# voltage_sensor_HiZ_LV_OpAmp.net
KiCad netlist of a schematic drawn in Altium Designer
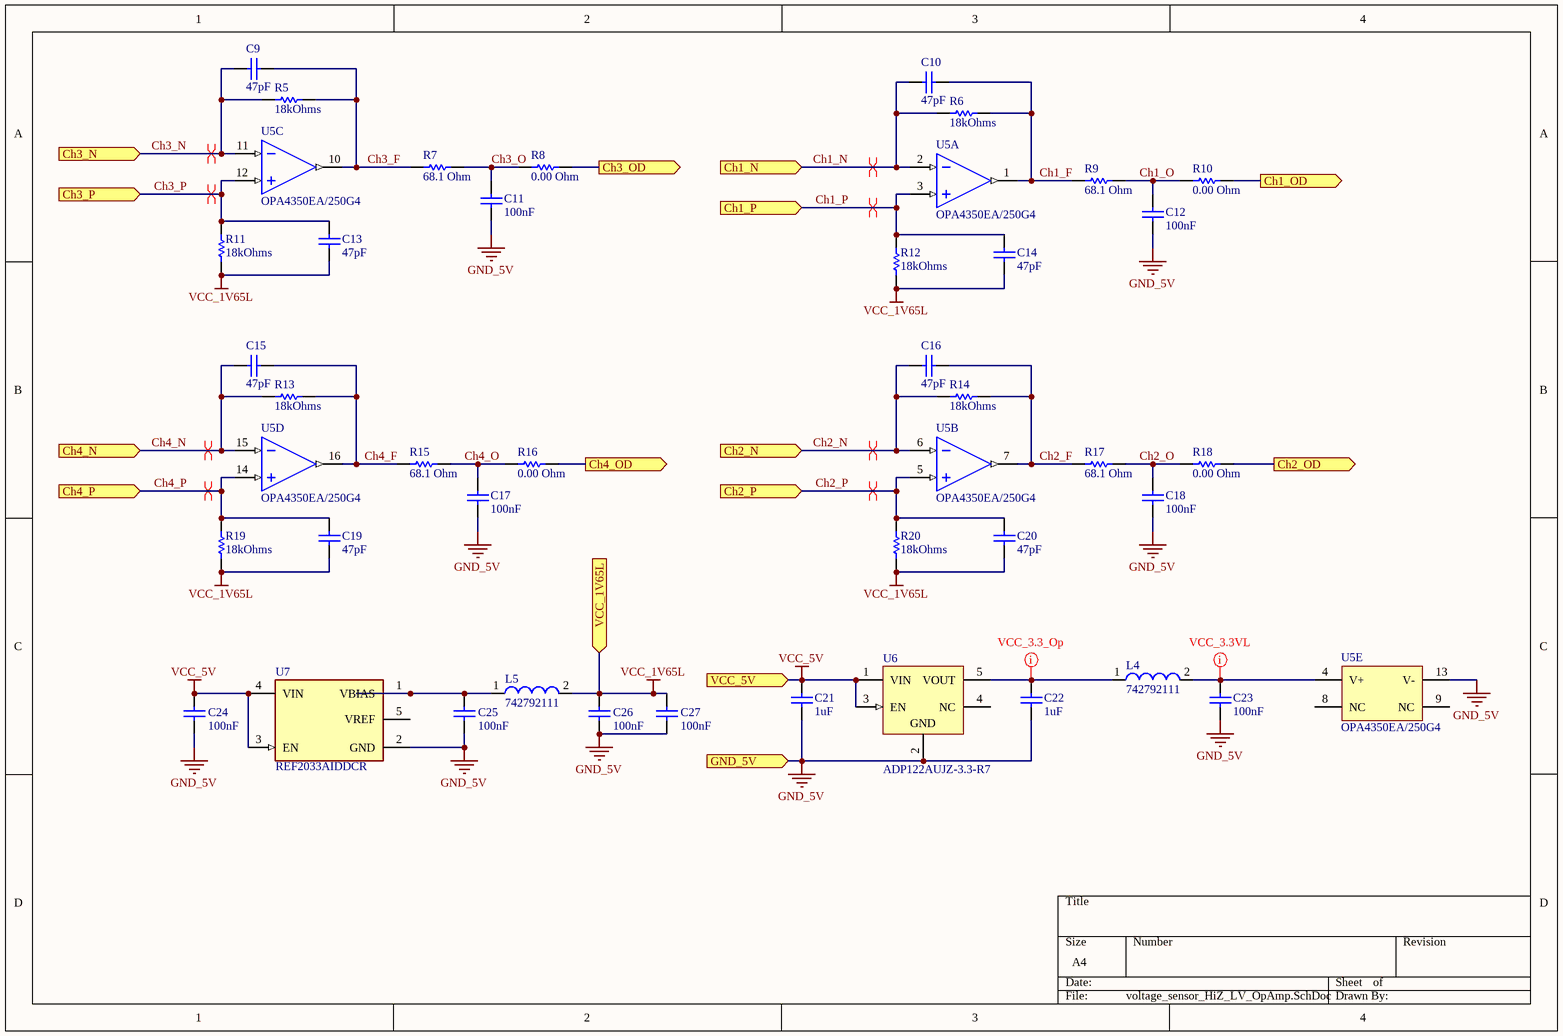
[diagram p0: voltage_sensor_HiZ_LV_OpAmp.SchDoc]

(export (version "E")
  (design (tool "Eeschema 10.0.6"))
  (components
    (comp (ref "C9")
      (value "47pF")
      (footprint "CAPC0603(1608)100_L")
      (description "CAP 47pF 50V ±5% 0603 (1608 Metric) Thickness 1mm SMD")
      (fields (field (name "TOLERANCE") "Â±5%") (field (name "Comment") "CAP 47pF 50V 0603(1608)"))
      (libsource (lib "Altium Content Vault") (part "CAP"))
    )
    (comp (ref "C10")
      (value "47pF")
      (footprint "CAPC0603(1608)100_L")
      (description "CAP 47pF 50V ±5% 0603 (1608 Metric) Thickness 1mm SMD")
      (fields (field (name "TOLERANCE") "Â±5%") (field (name "Comment") "CAP 47pF 50V 0603(1608)"))
      (libsource (lib "Altium Content Vault") (part "CAP"))
    )
    (comp (ref "C11")
      (value "100nF")
      (footprint "CAPC0603(1608)100_L")
      (description "CAP 100nF 10V ±10% 0603 (1608 Metric) Thickness 1mm SMD")
      (fields (field (name "TOLERANCE") "Â±10%") (field (name "Comment") "CAP 100nF 10V 0603(1608)"))
      (libsource (lib "Altium Content Vault") (part "CAP"))
    )
    (comp (ref "C12")
      (value "100nF")
      (footprint "CAPC0603(1608)100_L")
      (description "CAP 100nF 10V ±10% 0603 (1608 Metric) Thickness 1mm SMD")
      (fields (field (name "TOLERANCE") "Â±10%") (field (name "Comment") "CAP 100nF 10V 0603(1608)"))
      (libsource (lib "Altium Content Vault") (part "CAP"))
    )
    (comp (ref "C13")
      (value "47pF")
      (footprint "CAPC0603(1608)100_L")
      (description "CAP 47pF 50V ±5% 0603 (1608 Metric) Thickness 1mm SMD")
      (fields (field (name "TOLERANCE") "Â±5%") (field (name "Comment") "CAP 47pF 50V 0603(1608)"))
      (libsource (lib "Altium Content Vault") (part "CAP"))
    )
    (comp (ref "C14")
      (value "47pF")
      (footprint "CAPC0603(1608)100_L")
      (description "CAP 47pF 50V ±5% 0603 (1608 Metric) Thickness 1mm SMD")
      (fields (field (name "TOLERANCE") "Â±5%") (field (name "Comment") "CAP 47pF 50V 0603(1608)"))
      (libsource (lib "Altium Content Vault") (part "CAP"))
    )
    (comp (ref "C15")
      (value "47pF")
      (footprint "CAPC0603(1608)100_L")
      (description "CAP 47pF 50V ±5% 0603 (1608 Metric) Thickness 1mm SMD")
      (fields (field (name "TOLERANCE") "Â±5%") (field (name "Comment") "CAP 47pF 50V 0603(1608)"))
      (libsource (lib "Altium Content Vault") (part "CAP"))
    )
    (comp (ref "C16")
      (value "47pF")
      (footprint "CAPC0603(1608)100_L")
      (description "CAP 47pF 50V ±5% 0603 (1608 Metric) Thickness 1mm SMD")
      (fields (field (name "TOLERANCE") "Â±5%") (field (name "Comment") "CAP 47pF 50V 0603(1608)"))
      (libsource (lib "Altium Content Vault") (part "CAP"))
    )
    (comp (ref "C17")
      (value "100nF")
      (footprint "CAPC0603(1608)100_L")
      (description "CAP 100nF 10V ±10% 0603 (1608 Metric) Thickness 1mm SMD")
      (fields (field (name "TOLERANCE") "Â±10%") (field (name "Comment") "CAP 100nF 10V 0603(1608)"))
      (libsource (lib "Altium Content Vault") (part "CAP"))
    )
    (comp (ref "C18")
      (value "100nF")
      (footprint "CAPC0603(1608)100_L")
      (description "CAP 100nF 10V ±10% 0603 (1608 Metric) Thickness 1mm SMD")
      (fields (field (name "TOLERANCE") "Â±10%") (field (name "Comment") "CAP 100nF 10V 0603(1608)"))
      (libsource (lib "Altium Content Vault") (part "CAP"))
    )
    (comp (ref "C19")
      (value "47pF")
      (footprint "CAPC0603(1608)100_L")
      (description "CAP 47pF 50V ±5% 0603 (1608 Metric) Thickness 1mm SMD")
      (fields (field (name "TOLERANCE") "Â±5%") (field (name "Comment") "CAP 47pF 50V 0603(1608)"))
      (libsource (lib "Altium Content Vault") (part "CAP"))
    )
    (comp (ref "C20")
      (value "47pF")
      (footprint "CAPC0603(1608)100_L")
      (description "CAP 47pF 50V ±5% 0603 (1608 Metric) Thickness 1mm SMD")
      (fields (field (name "TOLERANCE") "Â±5%") (field (name "Comment") "CAP 47pF 50V 0603(1608)"))
      (libsource (lib "Altium Content Vault") (part "CAP"))
    )
    (comp (ref "C21")
      (value "1uF")
      (footprint "CAPC0603(1608)100_N")
      (description "CAP 1uF 50V ±20% 0603 (1608 Metric) Thickness 1mm SMD")
      (fields (field (name "TOLERANCE") "Â±20%") (field (name "Comment") "CAP 1uF 50V 0603(1608)"))
      (libsource (lib "Altium Content Vault") (part "CAP"))
    )
    (comp (ref "C22")
      (value "1uF")
      (footprint "CAPC0603(1608)100_N")
      (description "CAP 1uF 50V ±20% 0603 (1608 Metric) Thickness 1mm SMD")
      (fields (field (name "TOLERANCE") "Â±20%") (field (name "Comment") "CAP 1uF 50V 0603(1608)"))
      (libsource (lib "Altium Content Vault") (part "CAP"))
    )
    (comp (ref "C23")
      (value "100nF")
      (footprint "CAPC0603(1608)100_L")
      (description "CAP 100nF 10V ±10% 0603 (1608 Metric) Thickness 1mm SMD")
      (fields (field (name "TOLERANCE") "Â±10%") (field (name "Comment") "CAP 100nF 10V 0603(1608)"))
      (libsource (lib "Altium Content Vault") (part "CAP"))
    )
    (comp (ref "C24")
      (value "100nF")
      (footprint "CAPC0603(1608)100_N")
      (description "CAP 100nF 10V ±10% 0603 (1608 Metric) Thickness 1mm SMD")
      (fields (field (name "TOLERANCE") "Â±10%") (field (name "Comment") "CAP 100nF 10V 0603(1608)"))
      (libsource (lib "Altium Content Vault") (part "CAP"))
    )
    (comp (ref "C25")
      (value "100nF")
      (footprint "CAPC0603(1608)100_N")
      (description "CAP 100nF 10V ±10% 0603 (1608 Metric) Thickness 1mm SMD")
      (fields (field (name "TOLERANCE") "Â±10%") (field (name "Comment") "CAP 100nF 10V 0603(1608)"))
      (libsource (lib "Altium Content Vault") (part "CAP"))
    )
    (comp (ref "C26")
      (value "100nF")
      (footprint "CAPC0603(1608)100_L")
      (description "CAP 100nF 10V ±10% 0603 (1608 Metric) Thickness 1mm SMD")
      (fields (field (name "TOLERANCE") "Â±10%") (field (name "Comment") "CAP 100nF 10V 0603(1608)"))
      (libsource (lib "Altium Content Vault") (part "CAP"))
    )
    (comp (ref "C27")
      (value "100nF")
      (footprint "CAPC0603(1608)100_L")
      (description "CAP 100nF 10V ±10% 0603 (1608 Metric) Thickness 1mm SMD")
      (fields (field (name "TOLERANCE") "Â±10%") (field (name "Comment") "CAP 100nF 10V 0603(1608)"))
      (libsource (lib "Altium Content Vault") (part "CAP"))
    )
    (comp (ref "L4")
      (value "742792111")
      (footprint "SMD-1206")
      (description "SMD EMI Suppression Ferrite Bead WE-CBF, Z = 26 Ohm")
      (libsource (lib "Altium Content Vault") (part "PAS-IND-INDUCTOR-2"))
    )
    (comp (ref "L5")
      (value "742792111")
      (footprint "SMD-1206")
      (description "SMD EMI Suppression Ferrite Bead WE-CBF, Z = 26 Ohm")
      (libsource (lib "Altium Content Vault") (part "PAS-IND-INDUCTOR-2"))
    )
    (comp (ref "R5")
      (value "RC0603FR-0718KL")
      (footprint "RESC1608X55X25LL10T15")
      (description "Chip Resistor, 18 KOhm, +/- 1%, 0.1 W, -55 to 155 degC, 0603 (1608 Metric), RoHS, Tape and Reel")
      (fields
        (field (name "TOLERANCE") "1%")
        (field (name "MANUFACTURER") "Yageo")
        (field (name "RESISTANCE") "18kOhms")
      )
      (libsource (lib "Altium Content Vault") (part "RES-2"))
    )
    (comp (ref "R6")
      (value "RC0603FR-0718KL")
      (footprint "RESC1608X55X25LL10T15")
      (description "Chip Resistor, 18 KOhm, +/- 1%, 0.1 W, -55 to 155 degC, 0603 (1608 Metric), RoHS, Tape and Reel")
      (fields
        (field (name "TOLERANCE") "1%")
        (field (name "MANUFACTURER") "Yageo")
        (field (name "RESISTANCE") "18kOhms")
      )
      (libsource (lib "Altium Content Vault") (part "RES-2"))
    )
    (comp (ref "R7")
      (value "68.1 Ohm")
      (footprint "RESC1608X55X30LL15T15")
      (fields
        (field (name "MANUFACTURER") "Panasonic")
        (field (name "PART NUMBER") "ERJ-3EKF68R1V")
        (field (name "TOLERANCE") "1%")
      )
      (libsource (lib "Altium Content Vault") (part "RES"))
    )
    (comp (ref "R8")
      (value "0.00 Ohm")
      (footprint "RESC0603(1608)_L")
      (description "Jumper 0603 (1608 Metric)")
      (fields (field (name "POWER") "None") (field (name "Comment") "Jumper 0603(1608)"))
      (libsource (lib "Altium Content Vault") (part "RES"))
    )
    (comp (ref "R9")
      (value "68.1 Ohm")
      (footprint "RESC1608X55X30LL15T15")
      (fields
        (field (name "MANUFACTURER") "Panasonic")
        (field (name "PART NUMBER") "ERJ-3EKF68R1V")
        (field (name "TOLERANCE") "1%")
      )
      (libsource (lib "Altium Content Vault") (part "RES"))
    )
    (comp (ref "R10")
      (value "0.00 Ohm")
      (footprint "RESC0603(1608)_L")
      (description "Jumper 0603 (1608 Metric)")
      (fields (field (name "POWER") "None") (field (name "Comment") "Jumper 0603(1608)"))
      (libsource (lib "Altium Content Vault") (part "RES"))
    )
    (comp (ref "R11")
      (value "RC0603FR-0718KL")
      (footprint "RESC1608X55X25LL10T15")
      (description "Chip Resistor, 18 KOhm, +/- 1%, 0.1 W, -55 to 155 degC, 0603 (1608 Metric), RoHS, Tape and Reel")
      (fields
        (field (name "TOLERANCE") "1%")
        (field (name "MANUFACTURER") "Yageo")
        (field (name "RESISTANCE") "18kOhms")
      )
      (libsource (lib "Altium Content Vault") (part "RES-2"))
    )
    (comp (ref "R12")
      (value "RC0603FR-0718KL")
      (footprint "RESC1608X55X25LL10T15")
      (description "Chip Resistor, 18 KOhm, +/- 1%, 0.1 W, -55 to 155 degC, 0603 (1608 Metric), RoHS, Tape and Reel")
      (fields
        (field (name "TOLERANCE") "1%")
        (field (name "MANUFACTURER") "Yageo")
        (field (name "RESISTANCE") "18kOhms")
      )
      (libsource (lib "Altium Content Vault") (part "RES-2"))
    )
    (comp (ref "R13")
      (value "RC0603FR-0718KL")
      (footprint "RESC1608X55X25LL10T15")
      (description "Chip Resistor, 18 KOhm, +/- 1%, 0.1 W, -55 to 155 degC, 0603 (1608 Metric), RoHS, Tape and Reel")
      (fields
        (field (name "TOLERANCE") "1%")
        (field (name "MANUFACTURER") "Yageo")
        (field (name "RESISTANCE") "18kOhms")
      )
      (libsource (lib "Altium Content Vault") (part "RES-2"))
    )
    (comp (ref "R14")
      (value "RC0603FR-0718KL")
      (footprint "RESC1608X55X25LL10T15")
      (description "Chip Resistor, 18 KOhm, +/- 1%, 0.1 W, -55 to 155 degC, 0603 (1608 Metric), RoHS, Tape and Reel")
      (fields
        (field (name "TOLERANCE") "1%")
        (field (name "MANUFACTURER") "Yageo")
        (field (name "RESISTANCE") "18kOhms")
      )
      (libsource (lib "Altium Content Vault") (part "RES-2"))
    )
    (comp (ref "R15")
      (value "68.1 Ohm")
      (footprint "RESC1608X55X30LL15T15")
      (fields
        (field (name "MANUFACTURER") "Panasonic")
        (field (name "PART NUMBER") "ERJ-3EKF68R1V")
        (field (name "TOLERANCE") "1%")
      )
      (libsource (lib "Altium Content Vault") (part "RES"))
    )
    (comp (ref "R16")
      (value "0.00 Ohm")
      (footprint "RESC0603(1608)_L")
      (description "Jumper 0603 (1608 Metric)")
      (fields (field (name "POWER") "None") (field (name "Comment") "Jumper 0603(1608)"))
      (libsource (lib "Altium Content Vault") (part "RES"))
    )
    (comp (ref "R17")
      (value "68.1 Ohm")
      (footprint "RESC1608X55X30LL15T15")
      (fields
        (field (name "MANUFACTURER") "Panasonic")
        (field (name "PART NUMBER") "ERJ-3EKF68R1V")
        (field (name "TOLERANCE") "1%")
      )
      (libsource (lib "Altium Content Vault") (part "RES"))
    )
    (comp (ref "R18")
      (value "0.00 Ohm")
      (footprint "RESC0603(1608)_L")
      (description "Jumper 0603 (1608 Metric)")
      (fields (field (name "POWER") "None") (field (name "Comment") "Jumper 0603(1608)"))
      (libsource (lib "Altium Content Vault") (part "RES"))
    )
    (comp (ref "R19")
      (value "RC0603FR-0718KL")
      (footprint "RESC1608X55X25LL10T15")
      (description "Chip Resistor, 18 KOhm, +/- 1%, 0.1 W, -55 to 155 degC, 0603 (1608 Metric), RoHS, Tape and Reel")
      (fields
        (field (name "TOLERANCE") "1%")
        (field (name "MANUFACTURER") "Yageo")
        (field (name "RESISTANCE") "18kOhms")
      )
      (libsource (lib "Altium Content Vault") (part "RES-2"))
    )
    (comp (ref "R20")
      (value "RC0603FR-0718KL")
      (footprint "RESC1608X55X25LL10T15")
      (description "Chip Resistor, 18 KOhm, +/- 1%, 0.1 W, -55 to 155 degC, 0603 (1608 Metric), RoHS, Tape and Reel")
      (fields
        (field (name "TOLERANCE") "1%")
        (field (name "MANUFACTURER") "Yageo")
        (field (name "RESISTANCE") "18kOhms")
      )
      (libsource (lib "Altium Content Vault") (part "RES-2"))
    )
    (comp (ref "U5")
      (value "OPA4350EA/250G4")
      (footprint "TI-DBQ16_L")
      (fields (field (name "MANUFACTURER") "Texas Instruments"))
      (libsource (lib "Altium Content Vault") (part "TI-OPA4XXX-XX16"))
    )
    (comp (ref "U6")
      (value "ADP122AUJZ-3.3-R7")
      (footprint "ADI-UJ-5_N")
      (fields (field (name "MANUFACTURER") "Analog Devices"))
      (libsource (lib "Altium Content Vault") (part "ADI-ADP1XX-UJ-5"))
    )
    (comp (ref "U7")
      (value "REF2033AIDDCR")
      (footprint "FP-DDC0005A-IPC_C")
      (description "IC VREF SERIES 1.65V/3.3V 5SOT")
      (fields
        (field (name "OCTOPART") "https://octopart.com/ref2033aiddcr-texas+instruments-46921199")
        (field (name "MANUFACTURER") "Texas Instruments")
      )
      (libsource (lib "Altium Content Vault") (part "d9fc07eafd300fec854b4093a15f761"))
    )
  )
  (nets
    (net (code "1") (name "/Ch1_F") (class "Default")
      (node (ref "C10") (pin "2") (pinfunction "2_2") (pintype "passive"))
      (node (ref "R6") (pin "1") (pinfunction "1_1") (pintype "passive"))
      (node (ref "R9") (pin "2") (pinfunction "2_2") (pintype "passive"))
      (node (ref "U5") (pin "1") (pinfunction "OUT_A_1") (pintype "output"))
    )
    (net (code "2") (name "/Ch1_N") (class "Default")
      (node (ref "C10") (pin "1") (pinfunction "1_1") (pintype "passive"))
      (node (ref "R6") (pin "2") (pinfunction "2_2") (pintype "passive"))
      (node (ref "U5") (pin "2") (pinfunction "IN_A-_2") (pintype "input"))
    )
    (net (code "3") (name "/Ch1_O") (class "Default")
      (node (ref "C12") (pin "2") (pinfunction "2_2") (pintype "passive"))
      (node (ref "R10") (pin "2") (pinfunction "2_2") (pintype "passive"))
      (node (ref "R9") (pin "1") (pinfunction "1_1") (pintype "passive"))
    )
    (net (code "4") (name "/Ch1_OD") (class "Default")
      (node (ref "R10") (pin "1") (pinfunction "1_1") (pintype "passive"))
    )
    (net (code "5") (name "/Ch1_P") (class "Default")
      (node (ref "C14") (pin "1") (pinfunction "1_1") (pintype "passive"))
      (node (ref "R12") (pin "1") (pinfunction "1_1") (pintype "passive"))
      (node (ref "U5") (pin "3") (pinfunction "IN_A+_3") (pintype "input"))
    )
    (net (code "6") (name "/Ch2_F") (class "Default")
      (node (ref "C16") (pin "2") (pinfunction "2_2") (pintype "passive"))
      (node (ref "R14") (pin "1") (pinfunction "1_1") (pintype "passive"))
      (node (ref "R17") (pin "2") (pinfunction "2_2") (pintype "passive"))
      (node (ref "U5") (pin "7") (pinfunction "OUT_B_7") (pintype "output"))
    )
    (net (code "7") (name "/Ch2_N") (class "Default")
      (node (ref "C16") (pin "1") (pinfunction "1_1") (pintype "passive"))
      (node (ref "R14") (pin "2") (pinfunction "2_2") (pintype "passive"))
      (node (ref "U5") (pin "6") (pinfunction "IN_B-_6") (pintype "input"))
    )
    (net (code "8") (name "/Ch2_O") (class "Default")
      (node (ref "C18") (pin "2") (pinfunction "2_2") (pintype "passive"))
      (node (ref "R17") (pin "1") (pinfunction "1_1") (pintype "passive"))
      (node (ref "R18") (pin "2") (pinfunction "2_2") (pintype "passive"))
    )
    (net (code "9") (name "/Ch2_OD") (class "Default")
      (node (ref "R18") (pin "1") (pinfunction "1_1") (pintype "passive"))
    )
    (net (code "10") (name "/Ch2_P") (class "Default")
      (node (ref "C20") (pin "1") (pinfunction "1_1") (pintype "passive"))
      (node (ref "R20") (pin "1") (pinfunction "1_1") (pintype "passive"))
      (node (ref "U5") (pin "5") (pinfunction "IN_B+_5") (pintype "input"))
    )
    (net (code "11") (name "/Ch3_F") (class "Default")
      (node (ref "C9") (pin "2") (pinfunction "2_2") (pintype "passive"))
      (node (ref "R5") (pin "1") (pinfunction "1_1") (pintype "passive"))
      (node (ref "R7") (pin "2") (pinfunction "2_2") (pintype "passive"))
      (node (ref "U5") (pin "10") (pinfunction "OUT_C_10") (pintype "output"))
    )
    (net (code "12") (name "/Ch3_N") (class "Default")
      (node (ref "C9") (pin "1") (pinfunction "1_1") (pintype "passive"))
      (node (ref "R5") (pin "2") (pinfunction "2_2") (pintype "passive"))
      (node (ref "U5") (pin "11") (pinfunction "IN_C-_11") (pintype "input"))
    )
    (net (code "13") (name "/Ch3_O") (class "Default")
      (node (ref "C11") (pin "2") (pinfunction "2_2") (pintype "passive"))
      (node (ref "R7") (pin "1") (pinfunction "1_1") (pintype "passive"))
      (node (ref "R8") (pin "2") (pinfunction "2_2") (pintype "passive"))
    )
    (net (code "14") (name "/Ch3_OD") (class "Default")
      (node (ref "R8") (pin "1") (pinfunction "1_1") (pintype "passive"))
    )
    (net (code "15") (name "/Ch3_P") (class "Default")
      (node (ref "C13") (pin "1") (pinfunction "1_1") (pintype "passive"))
      (node (ref "R11") (pin "1") (pinfunction "1_1") (pintype "passive"))
      (node (ref "U5") (pin "12") (pinfunction "IN_C+_12") (pintype "input"))
    )
    (net (code "16") (name "/Ch4_F") (class "Default")
      (node (ref "C15") (pin "2") (pinfunction "2_2") (pintype "passive"))
      (node (ref "R13") (pin "1") (pinfunction "1_1") (pintype "passive"))
      (node (ref "R15") (pin "2") (pinfunction "2_2") (pintype "passive"))
      (node (ref "U5") (pin "16") (pinfunction "OUT_D_16") (pintype "output"))
    )
    (net (code "17") (name "/Ch4_N") (class "Default")
      (node (ref "C15") (pin "1") (pinfunction "1_1") (pintype "passive"))
      (node (ref "R13") (pin "2") (pinfunction "2_2") (pintype "passive"))
      (node (ref "U5") (pin "15") (pinfunction "IN_D-_15") (pintype "input"))
    )
    (net (code "18") (name "/Ch4_O") (class "Default")
      (node (ref "C17") (pin "2") (pinfunction "2_2") (pintype "passive"))
      (node (ref "R15") (pin "1") (pinfunction "1_1") (pintype "passive"))
      (node (ref "R16") (pin "2") (pinfunction "2_2") (pintype "passive"))
    )
    (net (code "19") (name "/Ch4_OD") (class "Default")
      (node (ref "R16") (pin "1") (pinfunction "1_1") (pintype "passive"))
    )
    (net (code "20") (name "/Ch4_P") (class "Default")
      (node (ref "C19") (pin "1") (pinfunction "1_1") (pintype "passive"))
      (node (ref "R19") (pin "1") (pinfunction "1_1") (pintype "passive"))
      (node (ref "U5") (pin "14") (pinfunction "IN_D+_14") (pintype "input"))
    )
    (net (code "21") (name "GND_5V") (class "Default")
      (node (ref "C11") (pin "1") (pinfunction "1_1") (pintype "passive"))
      (node (ref "C12") (pin "1") (pinfunction "1_1") (pintype "passive"))
      (node (ref "C17") (pin "1") (pinfunction "1_1") (pintype "passive"))
      (node (ref "C18") (pin "1") (pinfunction "1_1") (pintype "passive"))
      (node (ref "C21") (pin "1") (pinfunction "1_1") (pintype "passive"))
      (node (ref "C22") (pin "1") (pinfunction "1_1") (pintype "passive"))
      (node (ref "C23") (pin "1") (pinfunction "1_1") (pintype "passive"))
      (node (ref "C24") (pin "1") (pinfunction "1_1") (pintype "passive"))
      (node (ref "C25") (pin "1") (pinfunction "1_1") (pintype "passive"))
      (node (ref "C26") (pin "1") (pinfunction "1_1") (pintype "passive"))
      (node (ref "C27") (pin "1") (pinfunction "1_1") (pintype "passive"))
      (node (ref "U5") (pin "13") (pinfunction "V-_13") (pintype "power_in"))
      (node (ref "U6") (pin "2") (pinfunction "GND_2") (pintype "power_in"))
      (node (ref "U7") (pin "2") (pinfunction "GND_2") (pintype "power_in"))
    )
    (net (code "22") (name "Net-(U5E-V+)") (class "Default")
      (node (ref "C23") (pin "2") (pinfunction "2_2") (pintype "passive"))
      (node (ref "L4") (pin "2") (pinfunction "2_2") (pintype "passive"))
      (node (ref "U5") (pin "4") (pinfunction "V+_4") (pintype "power_in"))
    )
    (net (code "23") (name "Net-(U6-VOUT)") (class "Default")
      (node (ref "C22") (pin "2") (pinfunction "2_2") (pintype "passive"))
      (node (ref "L4") (pin "1") (pinfunction "1_1") (pintype "passive"))
      (node (ref "U6") (pin "5") (pinfunction "VOUT_5") (pintype "power_in"))
    )
    (net (code "24") (name "Net-(U7-VBIAS)") (class "Default")
      (node (ref "C25") (pin "2") (pinfunction "2_2") (pintype "passive"))
      (node (ref "L5") (pin "1") (pinfunction "1_1") (pintype "passive"))
      (node (ref "U7") (pin "1") (pinfunction "VBIAS_1") (pintype "power_in"))
    )
    (net (code "25") (name "VCC_1V65L") (class "Default")
      (node (ref "C13") (pin "2") (pinfunction "2_2") (pintype "passive"))
      (node (ref "C14") (pin "2") (pinfunction "2_2") (pintype "passive"))
      (node (ref "C19") (pin "2") (pinfunction "2_2") (pintype "passive"))
      (node (ref "C20") (pin "2") (pinfunction "2_2") (pintype "passive"))
      (node (ref "C26") (pin "2") (pinfunction "2_2") (pintype "passive"))
      (node (ref "C27") (pin "2") (pinfunction "2_2") (pintype "passive"))
      (node (ref "L5") (pin "2") (pinfunction "2_2") (pintype "passive"))
      (node (ref "R11") (pin "2") (pinfunction "2_2") (pintype "passive"))
      (node (ref "R12") (pin "2") (pinfunction "2_2") (pintype "passive"))
      (node (ref "R19") (pin "2") (pinfunction "2_2") (pintype "passive"))
      (node (ref "R20") (pin "2") (pinfunction "2_2") (pintype "passive"))
    )
    (net (code "26") (name "VCC_5V") (class "Default")
      (node (ref "C21") (pin "2") (pinfunction "2_2") (pintype "passive"))
      (node (ref "C24") (pin "2") (pinfunction "2_2") (pintype "passive"))
      (node (ref "U6") (pin "1") (pinfunction "VIN_1") (pintype "power_in"))
      (node (ref "U6") (pin "3") (pinfunction "EN_3") (pintype "input"))
      (node (ref "U7") (pin "3") (pinfunction "EN_3") (pintype "input"))
      (node (ref "U7") (pin "4") (pinfunction "VIN_4") (pintype "power_in"))
    )
    (net (code "27") (name "unconnected-(U5E-NC-Pad8)") (class "Default")
      (node (ref "U5") (pin "8") (pinfunction "NC_8") (pintype "passive"))
    )
    (net (code "28") (name "unconnected-(U5E-NC-Pad9)") (class "Default")
      (node (ref "U5") (pin "9") (pinfunction "NC_9") (pintype "passive"))
    )
    (net (code "29") (name "unconnected-(U6-NC-Pad4)") (class "Default")
      (node (ref "U6") (pin "4") (pinfunction "NC_4") (pintype "passive"))
    )
    (net (code "30") (name "unconnected-(U7-VREF-Pad5)") (class "Default")
      (node (ref "U7") (pin "5") (pinfunction "VREF_5") (pintype "power_in"))
    )
  )
)
